# Clock_Buffer.net
KiCad netlist of a schematic drawn in Altium Designer
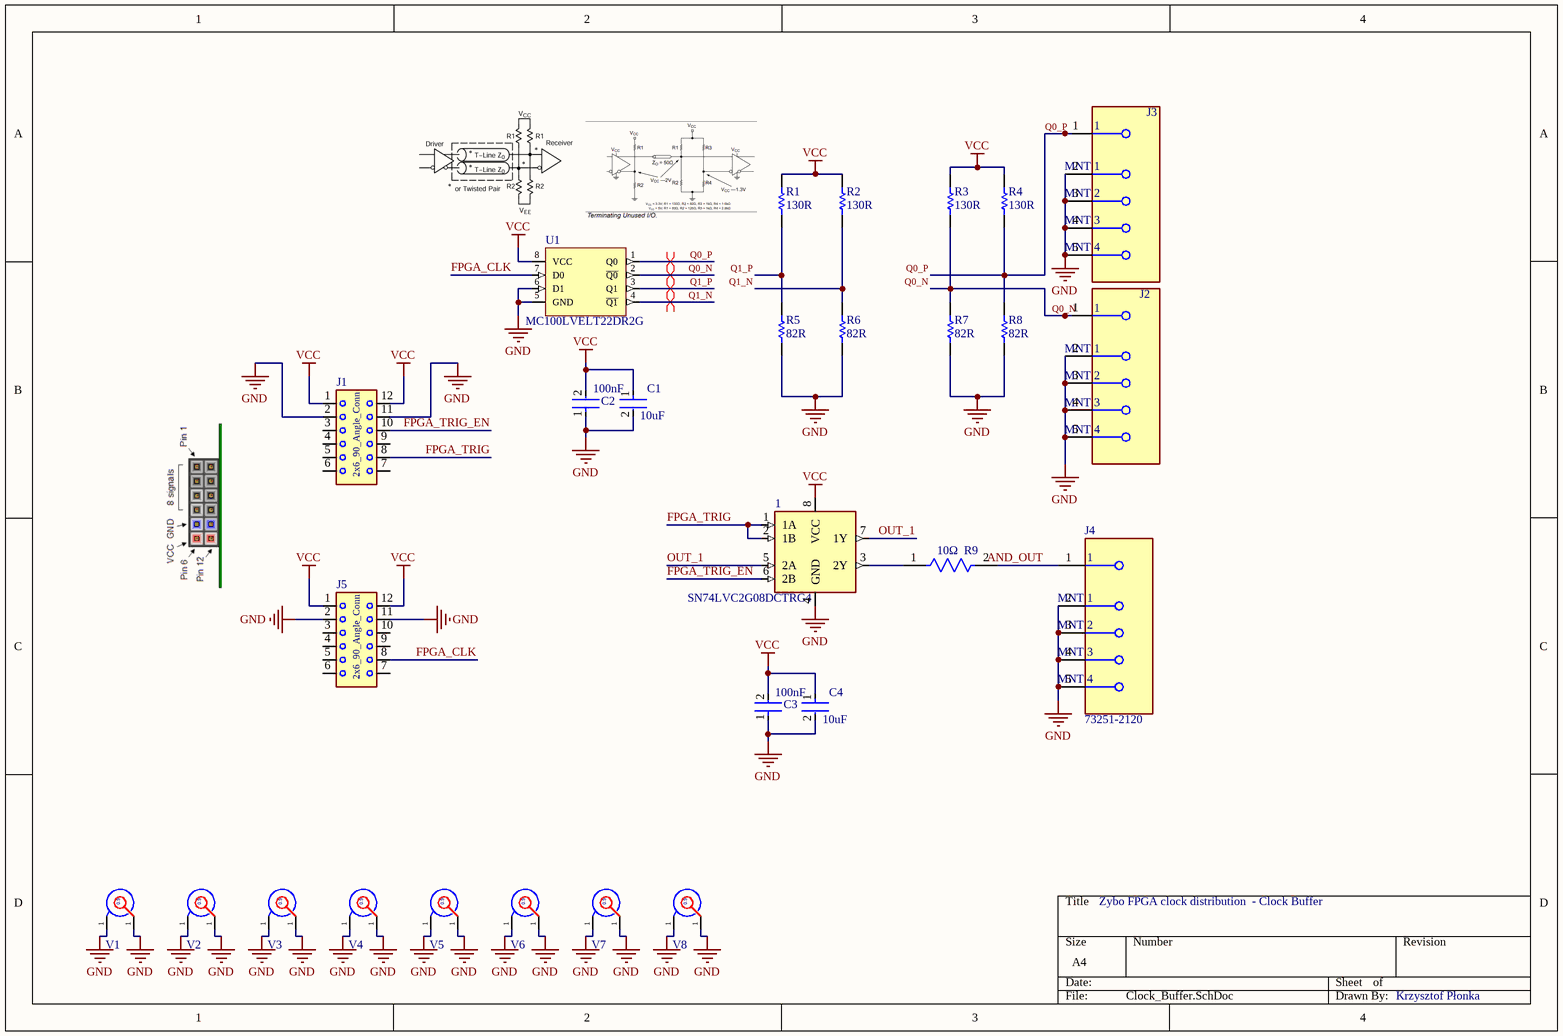
[diagram p0: Clock_Buffer.SchDoc]

(export (version "E")
  (design (tool "Eeschema 10.0.6"))
  (components
    (comp (ref "1")
      (value "SN74LVC2G08DCTRG4")
      (footprint "8-Pin SM8")
      (libsource (lib "Schematic-Lib-PhilsLab") (part "SN74LVC2G08DCTRG4"))
    )
    (comp (ref "C1")
      (value "10uF")
      (footprint "FP-GRM21B-0_2-e0_2_0_7-IPC_B")
      (description "Chip Multilayer Ceramic Capacitors for General Purpose, 0805, 10uF, X7R, 15%, 10%, 25V")
      (fields (field (name "Comment") "GRM21BZ71E106KE15K"))
      (libsource (lib "Altium Content Vault") (part "b4654b650e69147ec39a6b967a45e02"))
    )
    (comp (ref "C2")
      (value "100nF")
      (footprint "FP-GRM033-0_03-IPC_A")
      (description "Chip Multilayer Ceramic Capacitors for General Purpose, 0201, 0.10uF, X7R, 15%, 10%, 16V")
      (fields (field (name "Comment") "GRM033Z71C104KE14J"))
      (libsource (lib "Altium Content Vault") (part "b4654b650e69147ec39a6b967a45e02"))
    )
    (comp (ref "C3")
      (value "100nF")
      (footprint "FP-GRM033-0_03-IPC_A")
      (description "Chip Multilayer Ceramic Capacitors for General Purpose, 0201, 0.10uF, X7R, 15%, 10%, 16V")
      (fields (field (name "Comment") "GRM033Z71C104KE14J"))
      (libsource (lib "Altium Content Vault") (part "b4654b650e69147ec39a6b967a45e02"))
    )
    (comp (ref "C4")
      (value "10uF")
      (footprint "FP-GRM21B-0_2-e0_2_0_7-IPC_B")
      (description "Chip Multilayer Ceramic Capacitors for General Purpose, 0805, 10uF, X7R, 15%, 10%, 25V")
      (fields (field (name "Comment") "GRM21BZ71E106KE15K"))
      (libsource (lib "Altium Content Vault") (part "b4654b650e69147ec39a6b967a45e02"))
    )
    (comp (ref "J1")
      (value "2X6_Male_90_Angle_Conn")
      (footprint "2X6_Male_90_Angle_Conn")
      (description "2x16 right angle connector")
      (libsource (lib "Schematic-Lib-PhilsLab") (part "2X6_Male_90_Angle_Conn"))
    )
    (comp (ref "J2")
      (value "73251-2120")
      (footprint "FP-73251-2120-MFG")
      (description "CONN SMA JACK STR 50OHM EDGE MNT")
      (libsource (lib "Altium Content Vault") (part "c65b8a639cdaef1819ea20b5466f8fa"))
    )
    (comp (ref "J3")
      (value "73251-2120")
      (footprint "FP-73251-2120-MFG")
      (description "CONN SMA JACK STR 50OHM EDGE MNT")
      (libsource (lib "Altium Content Vault") (part "c65b8a639cdaef1819ea20b5466f8fa"))
    )
    (comp (ref "J4")
      (value "73251-2120")
      (footprint "FP-73251-2120-MFG")
      (description "CONN SMA JACK STR 50OHM EDGE MNT")
      (libsource (lib "Altium Content Vault") (part "c65b8a639cdaef1819ea20b5466f8fa"))
    )
    (comp (ref "J5")
      (value "2X6_Male_90_Angle_Conn")
      (footprint "2X6_Male_90_Angle_Conn")
      (description "2x16 right angle connector")
      (libsource (lib "Schematic-Lib-PhilsLab") (part "2X6_Male_90_Angle_Conn"))
    )
    (comp (ref "R1")
      (value "130R")
      (footprint "RESC0603X28X15ML05T05")
      (fields (field (name "PART NUMBER") "CRCW0201130RFNED") (field (name "MANUFACTURER") "Vishay Dale"))
      (libsource (lib "Altium Content Vault") (part "RES"))
    )
    (comp (ref "R2")
      (value "130R")
      (footprint "RESC0603X28X15ML05T05")
      (fields (field (name "PART NUMBER") "CRCW0201130RFNED") (field (name "MANUFACTURER") "Vishay Dale"))
      (libsource (lib "Altium Content Vault") (part "RES"))
    )
    (comp (ref "R3")
      (value "130R")
      (footprint "RESC0603X28X15ML05T05")
      (fields (field (name "PART NUMBER") "CRCW0201130RFNED") (field (name "MANUFACTURER") "Vishay Dale"))
      (libsource (lib "Altium Content Vault") (part "RES"))
    )
    (comp (ref "R4")
      (value "130R")
      (footprint "RESC0603X28X15ML05T05")
      (fields (field (name "PART NUMBER") "CRCW0201130RFNED") (field (name "MANUFACTURER") "Vishay Dale"))
      (libsource (lib "Altium Content Vault") (part "RES"))
    )
    (comp (ref "R5")
      (value "82R")
      (footprint "RESC0603X28X15ML05T05")
      (fields (field (name "MANUFACTURER") "Vishay Dale") (field (name "PART NUMBER") "CRCW020182R0FNED"))
      (libsource (lib "Altium Content Vault") (part "RES"))
    )
    (comp (ref "R6")
      (value "82R")
      (footprint "RESC0603X28X15ML05T05")
      (fields (field (name "MANUFACTURER") "Vishay Dale") (field (name "PART NUMBER") "CRCW020182R0FNED"))
      (libsource (lib "Altium Content Vault") (part "RES"))
    )
    (comp (ref "R7")
      (value "82R")
      (footprint "RESC0603X28X15ML05T05")
      (fields (field (name "MANUFACTURER") "Vishay Dale") (field (name "PART NUMBER") "CRCW020182R0FNED"))
      (libsource (lib "Altium Content Vault") (part "RES"))
    )
    (comp (ref "R8")
      (value "82R")
      (footprint "RESC0603X28X15ML05T05")
      (fields (field (name "MANUFACTURER") "Vishay Dale") (field (name "PART NUMBER") "CRCW020182R0FNED"))
      (libsource (lib "Altium Content Vault") (part "RES"))
    )
    (comp (ref "R9")
      (value "ERJ-1GNF10R0C")
      (footprint "FP-ERJ1GN-MFG")
      (fields (field (name "TOLERANCE") "1%") (field (name "RESISTANCE") "10Ω"))
      (libsource (lib "Altium Content Vault") (part "1029c3af85768c4190bb7ad29bc67b5"))
    )
    (comp (ref "U1")
      (value "MC100LVELT22DR2G")
      (footprint "MC100LVELT22DR2G")
      (description "SOIC-8, LVCMOS/LVTTL to LVPECL")
      (libsource (lib "Schematic-Lib-PhilsLab") (part "MC100LVELT22DR2G"))
    )
    (comp (ref "V1")
      (value "Copper_Via_09")
      (footprint "Copper_Via_09")
      (description "Copper Via 0.9mm hole")
      (libsource (lib "Schematic-Lib-PhilsLab") (part "Copper_Via_09"))
    )
    (comp (ref "V2")
      (value "Copper_Via_09")
      (footprint "Copper_Via_09")
      (description "Copper Via 0.9mm hole")
      (libsource (lib "Schematic-Lib-PhilsLab") (part "Copper_Via_09"))
    )
    (comp (ref "V3")
      (value "Copper_Via_09")
      (footprint "Copper_Via_09")
      (description "Copper Via 0.9mm hole")
      (libsource (lib "Schematic-Lib-PhilsLab") (part "Copper_Via_09"))
    )
    (comp (ref "V4")
      (value "Copper_Via_09")
      (footprint "Copper_Via_09")
      (description "Copper Via 0.9mm hole")
      (libsource (lib "Schematic-Lib-PhilsLab") (part "Copper_Via_09"))
    )
    (comp (ref "V5")
      (value "Copper_Via_09")
      (footprint "Copper_Via_09")
      (description "Copper Via 0.9mm hole")
      (libsource (lib "Schematic-Lib-PhilsLab") (part "Copper_Via_09"))
    )
    (comp (ref "V6")
      (value "Copper_Via_09")
      (footprint "Copper_Via_09")
      (description "Copper Via 0.9mm hole")
      (libsource (lib "Schematic-Lib-PhilsLab") (part "Copper_Via_09"))
    )
    (comp (ref "V7")
      (value "Copper_Via_09")
      (footprint "Copper_Via_09")
      (description "Copper Via 0.9mm hole")
      (libsource (lib "Schematic-Lib-PhilsLab") (part "Copper_Via_09"))
    )
    (comp (ref "V8")
      (value "Copper_Via_09")
      (footprint "Copper_Via_09")
      (description "Copper Via 0.9mm hole")
      (libsource (lib "Schematic-Lib-PhilsLab") (part "Copper_Via_09"))
    )
  )
  (nets
    (net (code "1") (name "/AND_OUT") (class "Default")
      (node (ref "J4") (pin "1") (pinfunction "1_1") (pintype "passive"))
      (node (ref "R9") (pin "2") (pinfunction "2_2") (pintype "passive"))
    )
    (net (code "2") (name "/FPGA_CLK") (class "Default")
      (node (ref "J5") (pin "8") (pintype "passive"))
      (node (ref "U1") (pin "7") (pinfunction "D0_7") (pintype "input"))
    )
    (net (code "3") (name "/FPGA_TRIG") (class "Default")
      (node (ref "1") (pin "1") (pinfunction "1A_1") (pintype "input"))
      (node (ref "1") (pin "2") (pinfunction "1B_2") (pintype "input"))
      (node (ref "J1") (pin "8") (pintype "passive"))
    )
    (net (code "4") (name "/FPGA_TRIG_EN") (class "Default")
      (node (ref "1") (pin "6") (pinfunction "2B_6") (pintype "input"))
      (node (ref "J1") (pin "10") (pintype "passive"))
    )
    (net (code "5") (name "/OUT_1") (class "Default")
      (node (ref "1") (pin "5") (pinfunction "2A_5") (pintype "input"))
      (node (ref "1") (pin "7") (pinfunction "1Y_7") (pintype "output"))
    )
    (net (code "6") (name "/Q0_N") (class "Default")
      (node (ref "J2") (pin "1") (pinfunction "1_1") (pintype "passive"))
      (node (ref "R3") (pin "1") (pinfunction "1_1") (pintype "passive"))
      (node (ref "R7") (pin "2") (pinfunction "2_2") (pintype "passive"))
      (node (ref "U1") (pin "2") (pinfunction "~{Q0}_2") (pintype "output"))
    )
    (net (code "7") (name "/Q0_P") (class "Default")
      (node (ref "J3") (pin "1") (pinfunction "1_1") (pintype "passive"))
      (node (ref "R4") (pin "1") (pinfunction "1_1") (pintype "passive"))
      (node (ref "R8") (pin "2") (pinfunction "2_2") (pintype "passive"))
      (node (ref "U1") (pin "1") (pinfunction "Q0_1") (pintype "output"))
    )
    (net (code "8") (name "/Q1_N") (class "Default")
      (node (ref "R2") (pin "1") (pinfunction "1_1") (pintype "passive"))
      (node (ref "R6") (pin "2") (pinfunction "2_2") (pintype "passive"))
      (node (ref "U1") (pin "4") (pinfunction "~{Q1}_4") (pintype "output"))
    )
    (net (code "9") (name "/Q1_P") (class "Default")
      (node (ref "R1") (pin "1") (pinfunction "1_1") (pintype "passive"))
      (node (ref "R5") (pin "2") (pinfunction "2_2") (pintype "passive"))
      (node (ref "U1") (pin "3") (pinfunction "Q1_3") (pintype "output"))
    )
    (net (code "10") (name "GND") (class "Default")
      (node (ref "1") (pin "4") (pinfunction "GND_4") (pintype "power_in"))
      (node (ref "C1") (pin "2") (pinfunction "2_2") (pintype "passive"))
      (node (ref "C2") (pin "1") (pinfunction "1_1") (pintype "passive"))
      (node (ref "C3") (pin "1") (pinfunction "1_1") (pintype "passive"))
      (node (ref "C4") (pin "2") (pinfunction "2_2") (pintype "passive"))
      (node (ref "J1") (pin "11") (pintype "passive"))
      (node (ref "J1") (pin "2") (pintype "passive"))
      (node (ref "J2") (pin "2") (pinfunction "MNT_1_2") (pintype "passive"))
      (node (ref "J2") (pin "3") (pinfunction "MNT_2_3") (pintype "passive"))
      (node (ref "J2") (pin "4") (pinfunction "MNT_3_4") (pintype "passive"))
      (node (ref "J2") (pin "5") (pinfunction "MNT_4_5") (pintype "passive"))
      (node (ref "J3") (pin "2") (pinfunction "MNT_1_2") (pintype "passive"))
      (node (ref "J3") (pin "3") (pinfunction "MNT_2_3") (pintype "passive"))
      (node (ref "J3") (pin "4") (pinfunction "MNT_3_4") (pintype "passive"))
      (node (ref "J3") (pin "5") (pinfunction "MNT_4_5") (pintype "passive"))
      (node (ref "J4") (pin "2") (pinfunction "MNT_1_2") (pintype "passive"))
      (node (ref "J4") (pin "3") (pinfunction "MNT_2_3") (pintype "passive"))
      (node (ref "J4") (pin "4") (pinfunction "MNT_3_4") (pintype "passive"))
      (node (ref "J4") (pin "5") (pinfunction "MNT_4_5") (pintype "passive"))
      (node (ref "J5") (pin "11") (pintype "passive"))
      (node (ref "J5") (pin "2") (pintype "passive"))
      (node (ref "R5") (pin "1") (pinfunction "1_1") (pintype "passive"))
      (node (ref "R6") (pin "1") (pinfunction "1_1") (pintype "passive"))
      (node (ref "R7") (pin "1") (pinfunction "1_1") (pintype "passive"))
      (node (ref "R8") (pin "1") (pinfunction "1_1") (pintype "passive"))
      (node (ref "U1") (pin "5") (pinfunction "GND_5") (pintype "power_in"))
      (node (ref "U1") (pin "6") (pinfunction "D1_6") (pintype "input"))
      (node (ref "V1") (pin "1") (pinfunction "1_1") (pintype "passive"))
      (node (ref "V2") (pin "1") (pinfunction "1_1") (pintype "passive"))
      (node (ref "V3") (pin "1") (pinfunction "1_1") (pintype "passive"))
      (node (ref "V4") (pin "1") (pinfunction "1_1") (pintype "passive"))
      (node (ref "V5") (pin "1") (pinfunction "1_1") (pintype "passive"))
      (node (ref "V6") (pin "1") (pinfunction "1_1") (pintype "passive"))
      (node (ref "V7") (pin "1") (pinfunction "1_1") (pintype "passive"))
      (node (ref "V8") (pin "1") (pinfunction "1_1") (pintype "passive"))
    )
    (net (code "11") (name "Net-(1-2Y)") (class "Default")
      (node (ref "1") (pin "3") (pinfunction "2Y_3") (pintype "output"))
      (node (ref "R9") (pin "1") (pinfunction "1_1") (pintype "passive"))
    )
    (net (code "12") (name "VCC") (class "Default")
      (node (ref "1") (pin "8") (pinfunction "VCC_8") (pintype "power_in"))
      (node (ref "C1") (pin "1") (pinfunction "1_1") (pintype "passive"))
      (node (ref "C2") (pin "2") (pinfunction "2_2") (pintype "passive"))
      (node (ref "C3") (pin "2") (pinfunction "2_2") (pintype "passive"))
      (node (ref "C4") (pin "1") (pinfunction "1_1") (pintype "passive"))
      (node (ref "J1") (pin "1") (pintype "passive"))
      (node (ref "J1") (pin "12") (pintype "passive"))
      (node (ref "J5") (pin "1") (pintype "passive"))
      (node (ref "J5") (pin "12") (pintype "passive"))
      (node (ref "R1") (pin "2") (pinfunction "2_2") (pintype "passive"))
      (node (ref "R2") (pin "2") (pinfunction "2_2") (pintype "passive"))
      (node (ref "R3") (pin "2") (pinfunction "2_2") (pintype "passive"))
      (node (ref "R4") (pin "2") (pinfunction "2_2") (pintype "passive"))
      (node (ref "U1") (pin "8") (pinfunction "VCC_8") (pintype "power_in"))
    )
    (net (code "13") (name "unconnected-(J1-Pad3)") (class "Default")
      (node (ref "J1") (pin "3") (pintype "passive"))
    )
    (net (code "14") (name "unconnected-(J1-Pad4)") (class "Default")
      (node (ref "J1") (pin "4") (pintype "passive"))
    )
    (net (code "15") (name "unconnected-(J1-Pad5)") (class "Default")
      (node (ref "J1") (pin "5") (pintype "passive"))
    )
    (net (code "16") (name "unconnected-(J1-Pad6)") (class "Default")
      (node (ref "J1") (pin "6") (pintype "passive"))
    )
    (net (code "17") (name "unconnected-(J1-Pad7)") (class "Default")
      (node (ref "J1") (pin "7") (pintype "passive"))
    )
    (net (code "18") (name "unconnected-(J1-Pad9)") (class "Default")
      (node (ref "J1") (pin "9") (pintype "passive"))
    )
    (net (code "19") (name "unconnected-(J5-Pad3)") (class "Default")
      (node (ref "J5") (pin "3") (pintype "passive"))
    )
    (net (code "20") (name "unconnected-(J5-Pad4)") (class "Default")
      (node (ref "J5") (pin "4") (pintype "passive"))
    )
    (net (code "21") (name "unconnected-(J5-Pad5)") (class "Default")
      (node (ref "J5") (pin "5") (pintype "passive"))
    )
    (net (code "22") (name "unconnected-(J5-Pad6)") (class "Default")
      (node (ref "J5") (pin "6") (pintype "passive"))
    )
    (net (code "23") (name "unconnected-(J5-Pad7)") (class "Default")
      (node (ref "J5") (pin "7") (pintype "passive"))
    )
    (net (code "24") (name "unconnected-(J5-Pad9)") (class "Default")
      (node (ref "J5") (pin "9") (pintype "passive"))
    )
    (net (code "25") (name "unconnected-(J5-Pad10)") (class "Default")
      (node (ref "J5") (pin "10") (pintype "passive"))
    )
  )
)
